# cadiz_mb_20140206_4.net
KiCad netlist of a schematic drawn in EAGLE
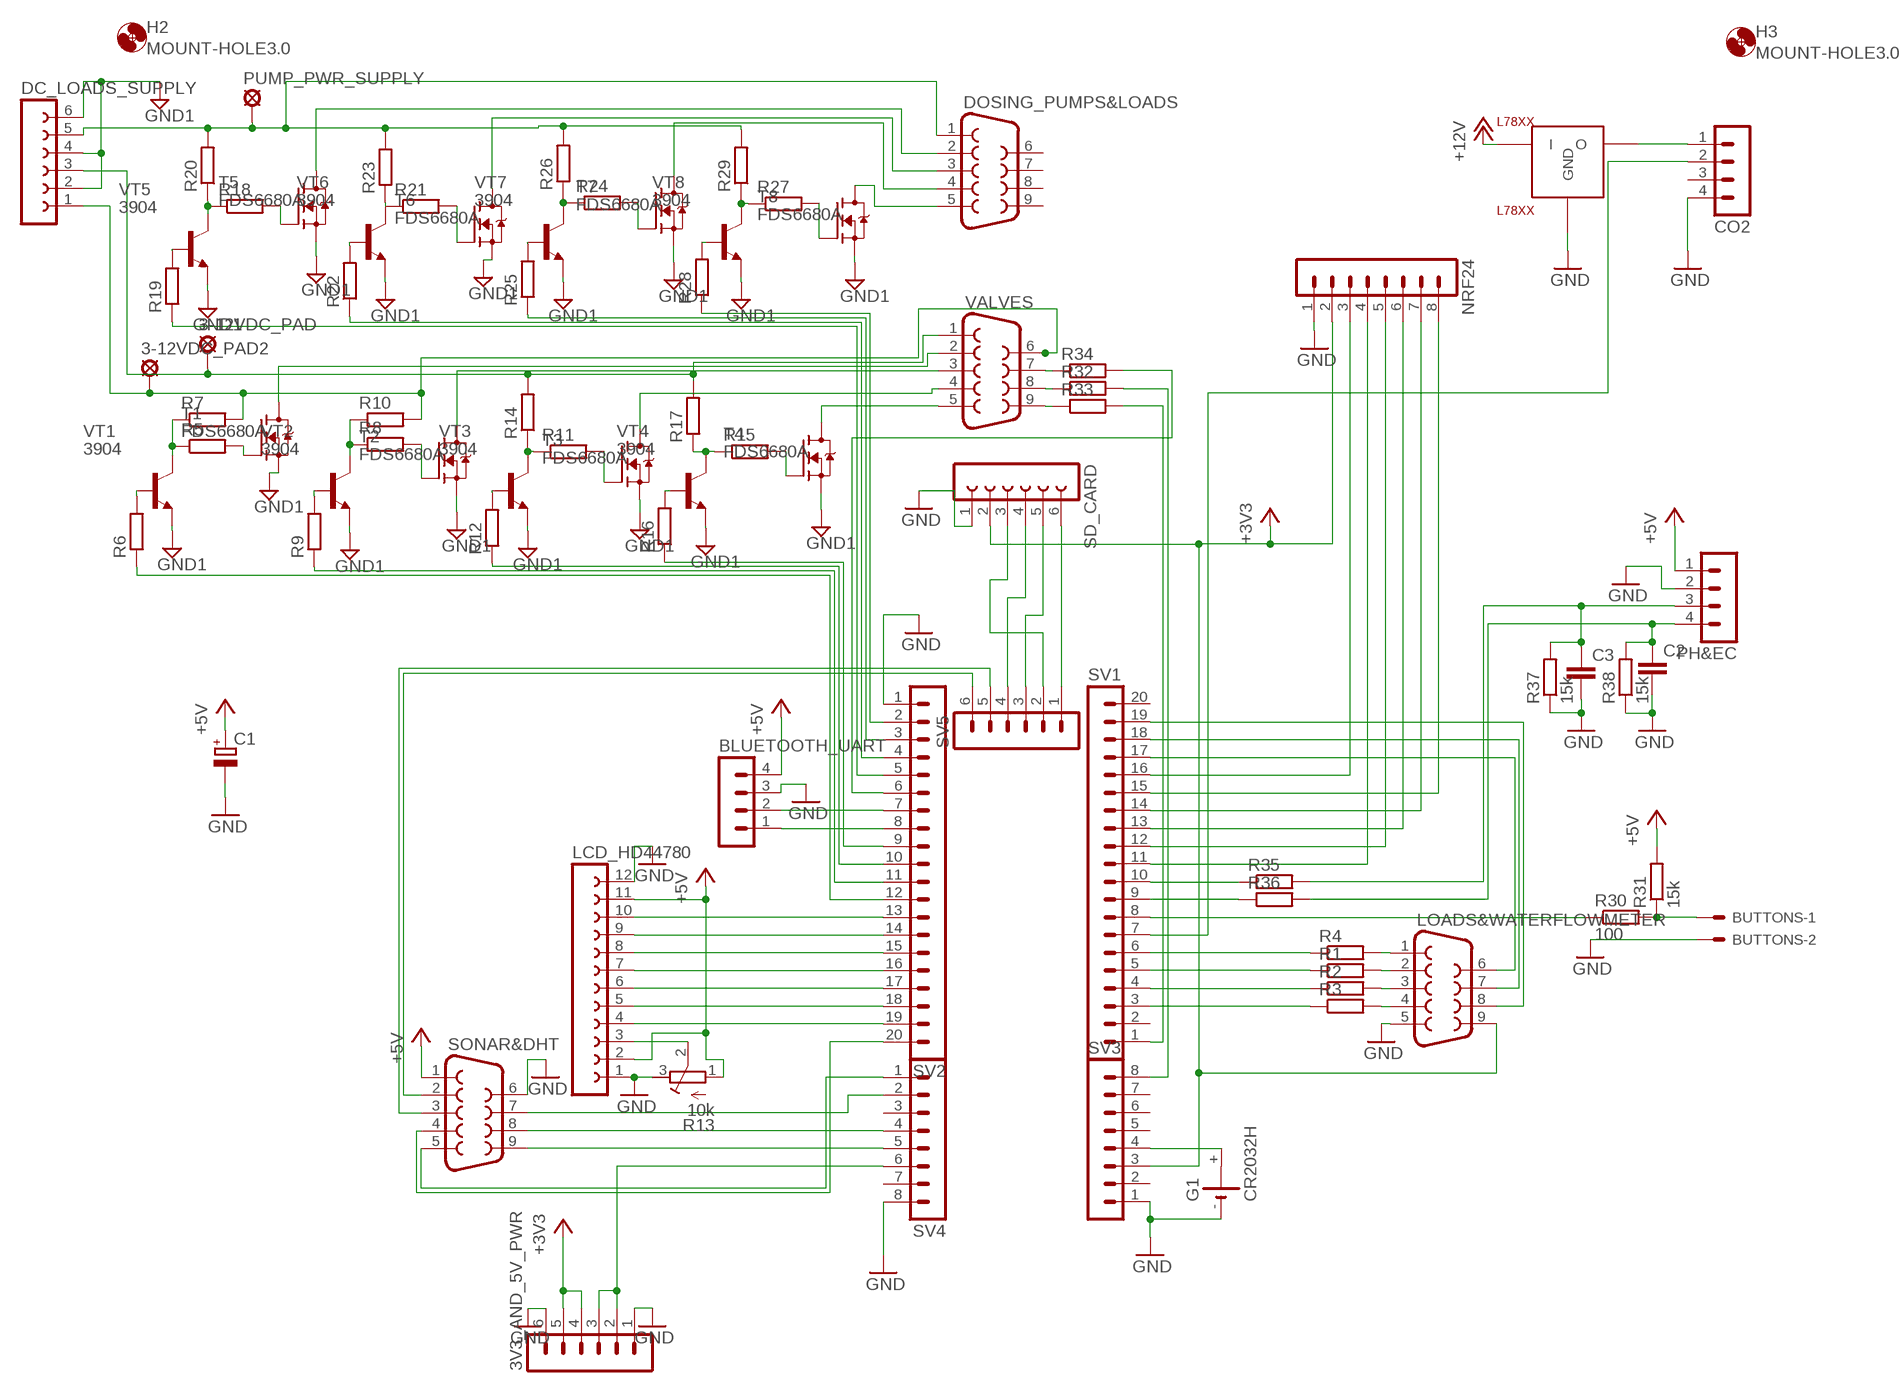
[diagram p0: schematic, sheet 1]

(export (version "E")
  (design (tool "Eeschema 10.0.6"))
  (components
    (comp (ref "3-12VDC_PAD")
      (value "LSP13")
      (footprint "eagle-import:LSP13")
      (libsource (lib "eagle-import") (part "LSP13"))
    )
    (comp (ref "3-12VDC_PAD2")
      (value "LSP13")
      (footprint "eagle-import:LSP13")
      (libsource (lib "eagle-import") (part "LSP13"))
    )
    (comp (ref "3V3_AND_5V_PWR")
      (value "MA06-1")
      (footprint "eagle-import:MA06-1")
      (libsource (lib "eagle-import") (part "MA06-1"))
    )
    (comp (ref "BLUETOOTH_UART")
      (value "MA04-1")
      (footprint "eagle-import:MA04-1")
      (libsource (lib "eagle-import") (part "MA04-1"))
    )
    (comp (ref "BUTTONS")
      (value "22-23-2021")
      (footprint "eagle-import:22-23-2021")
      (fields (field (name "MF") "MOLEX"))
      (libsource (lib "eagle-import") (part "22-23-2021"))
    )
    (comp (ref "C1")
      (value "CPOL-EUE5-13")
      (footprint "eagle-import:E5-13")
      (libsource (lib "eagle-import") (part "CPOL-EUE5-13"))
    )
    (comp (ref "C2")
      (value "C-EUC1206")
      (footprint "eagle-import:C1206")
      (libsource (lib "eagle-import") (part "C-EUC1206"))
    )
    (comp (ref "C3")
      (value "C-EUC1206")
      (footprint "eagle-import:C1206")
      (libsource (lib "eagle-import") (part "C-EUC1206"))
    )
    (comp (ref "CO2")
      (value "MA04-1")
      (footprint "eagle-import:MA04-1")
      (fields (field (name "OC_FARNELL") "unknown") (field (name "OC_NEWARK") "unknown"))
      (libsource (lib "eagle-import") (part "MA04-1"))
    )
    (comp (ref "DC_LOADS_SUPPLY")
      (value "FE06-1")
      (footprint "eagle-import:FE06")
      (libsource (lib "eagle-import") (part "FE06-1"))
    )
    (comp (ref "DOSING_PUMPS&LOADS")
      (value "F09HP")
      (footprint "eagle-import:F09HP")
      (libsource (lib "eagle-import") (part "F09HP"))
    )
    (comp (ref "G1")
      (value "CR2032H")
      (footprint "eagle-import:CR2032H")
      (libsource (lib "eagle-import") (part "CR2032H"))
    )
    (comp (ref "H2")
      (value "MOUNT-HOLE3.0")
      (footprint "eagle-import:3,0")
      (libsource (lib "eagle-import") (part "MOUNT-HOLE3.0"))
    )
    (comp (ref "H3")
      (value "MOUNT-HOLE3.0")
      (footprint "eagle-import:3,0")
      (libsource (lib "eagle-import") (part "MOUNT-HOLE3.0"))
    )
    (comp (ref "L7806")
      (value "L78XX")
      (footprint "eagle-import:TO220")
      (libsource (lib "eagle-import") (part "L78XX"))
    )
    (comp (ref "LCD_HD44780")
      (value "FE12-1")
      (footprint "eagle-import:FE12")
      (libsource (lib "eagle-import") (part "FE12-1"))
    )
    (comp (ref "LOADS&WATERFLOWMETER")
      (value "F09HP")
      (footprint "eagle-import:F09HP")
      (libsource (lib "eagle-import") (part "F09HP"))
    )
    (comp (ref "NRF24")
      (value "MA08-1")
      (footprint "eagle-import:MA08-1")
      (libsource (lib "eagle-import") (part "MA08-1"))
    )
    (comp (ref "PH&EC")
      (value "MA04-1")
      (footprint "eagle-import:MA04-1")
      (fields (field (name "OC_FARNELL") "unknown") (field (name "OC_NEWARK") "unknown"))
      (libsource (lib "eagle-import") (part "MA04-1"))
    )
    (comp (ref "PUMP_PWR_SUPPLY")
      (value "LSP13")
      (footprint "eagle-import:LSP13")
      (libsource (lib "eagle-import") (part "LSP13"))
    )
    (comp (ref "R1")
      (value "R-EU_M1206")
      (footprint "eagle-import:M1206")
      (libsource (lib "eagle-import") (part "R-EU_M1206"))
    )
    (comp (ref "R2")
      (value "R-EU_M1206")
      (footprint "eagle-import:M1206")
      (libsource (lib "eagle-import") (part "R-EU_M1206"))
    )
    (comp (ref "R3")
      (value "R-EU_M1206")
      (footprint "eagle-import:M1206")
      (libsource (lib "eagle-import") (part "R-EU_M1206"))
    )
    (comp (ref "R4")
      (value "R-EU_M1206")
      (footprint "eagle-import:M1206")
      (libsource (lib "eagle-import") (part "R-EU_M1206"))
    )
    (comp (ref "R5")
      (value "R-EU_M1206")
      (footprint "eagle-import:M1206")
      (libsource (lib "eagle-import") (part "R-EU_M1206"))
    )
    (comp (ref "R6")
      (value "R-EU_M1206")
      (footprint "eagle-import:M1206")
      (libsource (lib "eagle-import") (part "R-EU_M1206"))
    )
    (comp (ref "R7")
      (value "R-EU_M1206")
      (footprint "eagle-import:M1206")
      (libsource (lib "eagle-import") (part "R-EU_M1206"))
    )
    (comp (ref "R8")
      (value "R-EU_M1206")
      (footprint "eagle-import:M1206")
      (libsource (lib "eagle-import") (part "R-EU_M1206"))
    )
    (comp (ref "R9")
      (value "R-EU_M1206")
      (footprint "eagle-import:M1206")
      (libsource (lib "eagle-import") (part "R-EU_M1206"))
    )
    (comp (ref "R10")
      (value "R-EU_M1206")
      (footprint "eagle-import:M1206")
      (libsource (lib "eagle-import") (part "R-EU_M1206"))
    )
    (comp (ref "R11")
      (value "R-EU_M1206")
      (footprint "eagle-import:M1206")
      (libsource (lib "eagle-import") (part "R-EU_M1206"))
    )
    (comp (ref "R12")
      (value "R-EU_M1206")
      (footprint "eagle-import:M1206")
      (libsource (lib "eagle-import") (part "R-EU_M1206"))
    )
    (comp (ref "R13")
      (value "10k")
      (footprint "eagle-import:RTRIM3374")
      (libsource (lib "eagle-import") (part "R-TRIMM3374"))
    )
    (comp (ref "R14")
      (value "R-EU_M1206")
      (footprint "eagle-import:M1206")
      (libsource (lib "eagle-import") (part "R-EU_M1206"))
    )
    (comp (ref "R15")
      (value "R-EU_M1206")
      (footprint "eagle-import:M1206")
      (libsource (lib "eagle-import") (part "R-EU_M1206"))
    )
    (comp (ref "R16")
      (value "R-EU_M1206")
      (footprint "eagle-import:M1206")
      (libsource (lib "eagle-import") (part "R-EU_M1206"))
    )
    (comp (ref "R17")
      (value "R-EU_M1206")
      (footprint "eagle-import:M1206")
      (libsource (lib "eagle-import") (part "R-EU_M1206"))
    )
    (comp (ref "R18")
      (value "R-EU_M1206")
      (footprint "eagle-import:M1206")
      (libsource (lib "eagle-import") (part "R-EU_M1206"))
    )
    (comp (ref "R19")
      (value "R-EU_M1206")
      (footprint "eagle-import:M1206")
      (libsource (lib "eagle-import") (part "R-EU_M1206"))
    )
    (comp (ref "R20")
      (value "R-EU_M1206")
      (footprint "eagle-import:M1206")
      (libsource (lib "eagle-import") (part "R-EU_M1206"))
    )
    (comp (ref "R21")
      (value "R-EU_M1206")
      (footprint "eagle-import:M1206")
      (libsource (lib "eagle-import") (part "R-EU_M1206"))
    )
    (comp (ref "R22")
      (value "R-EU_M1206")
      (footprint "eagle-import:M1206")
      (libsource (lib "eagle-import") (part "R-EU_M1206"))
    )
    (comp (ref "R23")
      (value "R-EU_M1206")
      (footprint "eagle-import:M1206")
      (libsource (lib "eagle-import") (part "R-EU_M1206"))
    )
    (comp (ref "R24")
      (value "R-EU_M1206")
      (footprint "eagle-import:M1206")
      (libsource (lib "eagle-import") (part "R-EU_M1206"))
    )
    (comp (ref "R25")
      (value "R-EU_M1206")
      (footprint "eagle-import:M1206")
      (libsource (lib "eagle-import") (part "R-EU_M1206"))
    )
    (comp (ref "R26")
      (value "R-EU_M1206")
      (footprint "eagle-import:M1206")
      (libsource (lib "eagle-import") (part "R-EU_M1206"))
    )
    (comp (ref "R27")
      (value "R-EU_M1206")
      (footprint "eagle-import:M1206")
      (libsource (lib "eagle-import") (part "R-EU_M1206"))
    )
    (comp (ref "R28")
      (value "R-EU_M1206")
      (footprint "eagle-import:M1206")
      (libsource (lib "eagle-import") (part "R-EU_M1206"))
    )
    (comp (ref "R29")
      (value "R-EU_M1206")
      (footprint "eagle-import:M1206")
      (libsource (lib "eagle-import") (part "R-EU_M1206"))
    )
    (comp (ref "R30")
      (value "100")
      (footprint "eagle-import:M1206")
      (libsource (lib "eagle-import") (part "R-EU_M1206"))
    )
    (comp (ref "R31")
      (value "15k")
      (footprint "eagle-import:M1206")
      (libsource (lib "eagle-import") (part "R-EU_M1206"))
    )
    (comp (ref "R32")
      (value "R-EU_M1206")
      (footprint "eagle-import:M1206")
      (libsource (lib "eagle-import") (part "R-EU_M1206"))
    )
    (comp (ref "R33")
      (value "R-EU_M1206")
      (footprint "eagle-import:M1206")
      (libsource (lib "eagle-import") (part "R-EU_M1206"))
    )
    (comp (ref "R34")
      (value "R-EU_M1206")
      (footprint "eagle-import:M1206")
      (libsource (lib "eagle-import") (part "R-EU_M1206"))
    )
    (comp (ref "R35")
      (value "R-EU_M1206")
      (footprint "eagle-import:M1206")
      (libsource (lib "eagle-import") (part "R-EU_M1206"))
    )
    (comp (ref "R36")
      (value "R-EU_M1206")
      (footprint "eagle-import:M1206")
      (libsource (lib "eagle-import") (part "R-EU_M1206"))
    )
    (comp (ref "R37")
      (value "15k")
      (footprint "eagle-import:M1206")
      (libsource (lib "eagle-import") (part "R-EU_M1206"))
    )
    (comp (ref "R38")
      (value "15k")
      (footprint "eagle-import:M1206")
      (libsource (lib "eagle-import") (part "R-EU_M1206"))
    )
    (comp (ref "SD_CARD")
      (value "FE06-1")
      (footprint "eagle-import:FE06")
      (libsource (lib "eagle-import") (part "FE06-1"))
    )
    (comp (ref "SONAR&DHT")
      (value "F09HP")
      (footprint "eagle-import:F09HP")
      (libsource (lib "eagle-import") (part "F09HP"))
    )
    (comp (ref "SV1")
      (value "MA20-1")
      (footprint "eagle-import:MA20-1")
      (libsource (lib "eagle-import") (part "MA20-1"))
    )
    (comp (ref "SV2")
      (value "MA20-1")
      (footprint "eagle-import:MA20-1")
      (libsource (lib "eagle-import") (part "MA20-1"))
    )
    (comp (ref "SV3")
      (value "MA08-1")
      (footprint "eagle-import:MA08-1")
      (libsource (lib "eagle-import") (part "MA08-1"))
    )
    (comp (ref "SV4")
      (value "MA08-1")
      (footprint "eagle-import:MA08-1")
      (libsource (lib "eagle-import") (part "MA08-1"))
    )
    (comp (ref "SV5")
      (value "MA06-1")
      (footprint "eagle-import:MA06-1")
      (libsource (lib "eagle-import") (part "MA06-1"))
    )
    (comp (ref "T1")
      (value "FDS6680A")
      (footprint "eagle-import:SO8")
      (libsource (lib "eagle-import") (part "FDS6680A_SOP8"))
    )
    (comp (ref "T2")
      (value "FDS6680A")
      (footprint "eagle-import:SO8")
      (libsource (lib "eagle-import") (part "FDS6680A_SOP8"))
    )
    (comp (ref "T3")
      (value "FDS6680A")
      (footprint "eagle-import:SO8")
      (libsource (lib "eagle-import") (part "FDS6680A_SOP8"))
    )
    (comp (ref "T4")
      (value "FDS6680A")
      (footprint "eagle-import:SO8")
      (libsource (lib "eagle-import") (part "FDS6680A_SOP8"))
    )
    (comp (ref "T5")
      (value "FDS6680A")
      (footprint "eagle-import:SO8")
      (libsource (lib "eagle-import") (part "FDS6680A_SOP8"))
    )
    (comp (ref "T6")
      (value "FDS6680A")
      (footprint "eagle-import:SO8")
      (libsource (lib "eagle-import") (part "FDS6680A_SOP8"))
    )
    (comp (ref "T7")
      (value "FDS6680A")
      (footprint "eagle-import:SO8")
      (libsource (lib "eagle-import") (part "FDS6680A_SOP8"))
    )
    (comp (ref "T8")
      (value "FDS6680A")
      (footprint "eagle-import:SO8")
      (libsource (lib "eagle-import") (part "FDS6680A_SOP8"))
    )
    (comp (ref "VALVES")
      (value "F09HP")
      (footprint "eagle-import:F09HP")
      (libsource (lib "eagle-import") (part "F09HP"))
    )
    (comp (ref "VT1")
      (value "3904")
      (footprint "eagle-import:SOT23")
      (libsource (lib "eagle-import") (part "BC847"))
    )
    (comp (ref "VT2")
      (value "3904")
      (footprint "eagle-import:SOT23")
      (libsource (lib "eagle-import") (part "BC847"))
    )
    (comp (ref "VT3")
      (value "3904")
      (footprint "eagle-import:SOT23")
      (libsource (lib "eagle-import") (part "BC847"))
    )
    (comp (ref "VT4")
      (value "3904")
      (footprint "eagle-import:SOT23")
      (libsource (lib "eagle-import") (part "BC847"))
    )
    (comp (ref "VT5")
      (value "3904")
      (footprint "eagle-import:SOT23")
      (libsource (lib "eagle-import") (part "BC847"))
    )
    (comp (ref "VT6")
      (value "3904")
      (footprint "eagle-import:SOT23")
      (libsource (lib "eagle-import") (part "BC847"))
    )
    (comp (ref "VT7")
      (value "3904")
      (footprint "eagle-import:SOT23")
      (libsource (lib "eagle-import") (part "BC847"))
    )
    (comp (ref "VT8")
      (value "3904")
      (footprint "eagle-import:SOT23")
      (libsource (lib "eagle-import") (part "BC847"))
    )
  )
  (nets
    (net (code "1") (name "+3V3") (class "Default")
      (node (ref "3V3_AND_5V_PWR") (pin "4") (pinfunction "4_4") (pintype "passive"))
      (node (ref "3V3_AND_5V_PWR") (pin "5") (pinfunction "5_5") (pintype "passive"))
      (node (ref "LOADS&WATERFLOWMETER") (pin "9") (pinfunction "9_9") (pintype "passive"))
      (node (ref "NRF24") (pin "2") (pinfunction "2_2") (pintype "passive"))
      (node (ref "SD_CARD") (pin "2") (pinfunction "2_2") (pintype "passive"))
      (node (ref "SV3") (pin "3") (pinfunction "3_3") (pintype "passive"))
    )
    (net (code "2") (name "+5V") (class "Default")
      (node (ref "BLUETOOTH_UART") (pin "4") (pinfunction "4_4") (pintype "passive"))
      (node (ref "C1") (pin "+") (pinfunction "+_+") (pintype "passive"))
      (node (ref "LCD_HD44780") (pin "11") (pinfunction "11_11") (pintype "passive"))
      (node (ref "LCD_HD44780") (pin "2") (pinfunction "2_2") (pintype "passive"))
      (node (ref "PH&EC") (pin "1") (pinfunction "1_1") (pintype "passive"))
      (node (ref "R13") (pin "1") (pinfunction "E_1") (pintype "passive"))
      (node (ref "R31") (pin "2") (pinfunction "2_2") (pintype "passive"))
      (node (ref "SONAR&DHT") (pin "1") (pinfunction "1_1") (pintype "passive"))
    )
    (net (code "3") (name "+12V") (class "Default")
      (node (ref "L7806") (pin "IN") (pinfunction "I_IN") (pintype "power_in"))
    )
    (net (code "4") (name "GND") (class "Default")
      (node (ref "3V3_AND_5V_PWR") (pin "1") (pinfunction "1_1") (pintype "passive"))
      (node (ref "3V3_AND_5V_PWR") (pin "6") (pinfunction "6_6") (pintype "passive"))
      (node (ref "BLUETOOTH_UART") (pin "3") (pinfunction "3_3") (pintype "passive"))
      (node (ref "BUTTONS") (pin "2") (pinfunction "S_2") (pintype "passive"))
      (node (ref "C1") (pin "-") (pinfunction "-_-") (pintype "passive"))
      (node (ref "C2") (pin "2") (pinfunction "2_2") (pintype "passive"))
      (node (ref "C3") (pin "2") (pinfunction "2_2") (pintype "passive"))
      (node (ref "CO2") (pin "4") (pinfunction "4_4") (pintype "passive"))
      (node (ref "G1") (pin "-") (pinfunction "-_-") (pintype "passive"))
      (node (ref "L7806") (pin "GND") (pinfunction "GND_GND") (pintype "power_in"))
      (node (ref "LCD_HD44780") (pin "1") (pinfunction "1_1") (pintype "passive"))
      (node (ref "LCD_HD44780") (pin "12") (pinfunction "12_12") (pintype "passive"))
      (node (ref "LOADS&WATERFLOWMETER") (pin "5") (pinfunction "5_5") (pintype "passive"))
      (node (ref "NRF24") (pin "1") (pinfunction "1_1") (pintype "passive"))
      (node (ref "PH&EC") (pin "2") (pinfunction "2_2") (pintype "passive"))
      (node (ref "R13") (pin "3") (pinfunction "A_3") (pintype "passive"))
      (node (ref "R37") (pin "1") (pinfunction "1_1") (pintype "passive"))
      (node (ref "R38") (pin "1") (pinfunction "1_1") (pintype "passive"))
      (node (ref "SD_CARD") (pin "1") (pinfunction "1_1") (pintype "passive"))
      (node (ref "SONAR&DHT") (pin "6") (pinfunction "6_6") (pintype "passive"))
      (node (ref "SV2") (pin "1") (pinfunction "1_1") (pintype "passive"))
      (node (ref "SV3") (pin "1") (pinfunction "1_1") (pintype "passive"))
      (node (ref "SV4") (pin "8") (pinfunction "8_8") (pintype "passive"))
    )
    (net (code "5") (name "GND1") (class "Default")
      (node (ref "DC_LOADS_SUPPLY") (pin "2") (pinfunction "2_2") (pintype "passive"))
      (node (ref "DC_LOADS_SUPPLY") (pin "4") (pinfunction "4_4") (pintype "passive"))
      (node (ref "DC_LOADS_SUPPLY") (pin "6") (pinfunction "6_6") (pintype "passive"))
      (node (ref "T1") (pin "SOURCE") (pinfunction "S_SOURCE") (pintype "passive"))
      (node (ref "T2") (pin "SOURCE") (pinfunction "S_SOURCE") (pintype "passive"))
      (node (ref "T3") (pin "SOURCE") (pinfunction "S_SOURCE") (pintype "passive"))
      (node (ref "T4") (pin "SOURCE") (pinfunction "S_SOURCE") (pintype "passive"))
      (node (ref "T5") (pin "SOURCE") (pinfunction "S_SOURCE") (pintype "passive"))
      (node (ref "T6") (pin "SOURCE") (pinfunction "S_SOURCE") (pintype "passive"))
      (node (ref "T7") (pin "SOURCE") (pinfunction "S_SOURCE") (pintype "passive"))
      (node (ref "T8") (pin "SOURCE") (pinfunction "S_SOURCE") (pintype "passive"))
      (node (ref "VT1") (pin "2") (pinfunction "E_2") (pintype "passive"))
      (node (ref "VT2") (pin "2") (pinfunction "E_2") (pintype "passive"))
      (node (ref "VT3") (pin "2") (pinfunction "E_2") (pintype "passive"))
      (node (ref "VT4") (pin "2") (pinfunction "E_2") (pintype "passive"))
      (node (ref "VT5") (pin "2") (pinfunction "E_2") (pintype "passive"))
      (node (ref "VT6") (pin "2") (pinfunction "E_2") (pintype "passive"))
      (node (ref "VT7") (pin "2") (pinfunction "E_2") (pintype "passive"))
      (node (ref "VT8") (pin "2") (pinfunction "E_2") (pintype "passive"))
    )
    (net (code "6") (name "Net-(3-12VDC_PAD-PadMP)") (class "Default")
      (node (ref "3-12VDC_PAD") (pin "MP") (pinfunction "MP_MP") (pintype "passive"))
      (node (ref "DC_LOADS_SUPPLY") (pin "3") (pinfunction "3_3") (pintype "passive"))
      (node (ref "R14") (pin "2") (pinfunction "2_2") (pintype "passive"))
      (node (ref "R17") (pin "2") (pinfunction "2_2") (pintype "passive"))
      (node (ref "VALVES") (pin "1") (pinfunction "1_1") (pintype "passive"))
    )
    (net (code "7") (name "Net-(3-12VDC_PAD2-PadMP)") (class "Default")
      (node (ref "3-12VDC_PAD2") (pin "MP") (pinfunction "MP_MP") (pintype "passive"))
      (node (ref "DC_LOADS_SUPPLY") (pin "1") (pinfunction "1_1") (pintype "passive"))
      (node (ref "R10") (pin "2") (pinfunction "2_2") (pintype "passive"))
      (node (ref "R7") (pin "2") (pinfunction "2_2") (pintype "passive"))
      (node (ref "VALVES") (pin "6") (pinfunction "6_6") (pintype "passive"))
    )
    (net (code "8") (name "Net-(3V3_AND_5V_PWR-Pad2)") (class "Default")
      (node (ref "3V3_AND_5V_PWR") (pin "2") (pinfunction "2_2") (pintype "passive"))
      (node (ref "3V3_AND_5V_PWR") (pin "3") (pinfunction "3_3") (pintype "passive"))
      (node (ref "SV4") (pin "6") (pinfunction "6_6") (pintype "passive"))
    )
    (net (code "9") (name "Net-(BLUETOOTH_UART-Pad1)") (class "Default")
      (node (ref "BLUETOOTH_UART") (pin "1") (pinfunction "1_1") (pintype "passive"))
      (node (ref "SV2") (pin "8") (pinfunction "8_8") (pintype "passive"))
    )
    (net (code "10") (name "Net-(BLUETOOTH_UART-Pad2)") (class "Default")
      (node (ref "BLUETOOTH_UART") (pin "2") (pinfunction "2_2") (pintype "passive"))
      (node (ref "SV2") (pin "7") (pinfunction "7_7") (pintype "passive"))
    )
    (net (code "11") (name "Net-(BUTTONSA-S)") (class "Default")
      (node (ref "BUTTONS") (pin "1") (pinfunction "S_1") (pintype "passive"))
      (node (ref "R30") (pin "2") (pinfunction "2_2") (pintype "passive"))
      (node (ref "R31") (pin "1") (pinfunction "1_1") (pintype "passive"))
    )
    (net (code "12") (name "Net-(C2-Pad1)") (class "Default")
      (node (ref "C2") (pin "1") (pinfunction "1_1") (pintype "passive"))
      (node (ref "PH&EC") (pin "4") (pinfunction "4_4") (pintype "passive"))
      (node (ref "R36") (pin "2") (pinfunction "2_2") (pintype "passive"))
      (node (ref "R38") (pin "2") (pinfunction "2_2") (pintype "passive"))
    )
    (net (code "13") (name "Net-(C3-Pad1)") (class "Default")
      (node (ref "C3") (pin "1") (pinfunction "1_1") (pintype "passive"))
      (node (ref "PH&EC") (pin "3") (pinfunction "3_3") (pintype "passive"))
      (node (ref "R35") (pin "2") (pinfunction "2_2") (pintype "passive"))
      (node (ref "R37") (pin "2") (pinfunction "2_2") (pintype "passive"))
    )
    (net (code "14") (name "Net-(CO2-Pad2)") (class "Default")
      (node (ref "CO2") (pin "2") (pinfunction "2_2") (pintype "passive"))
      (node (ref "SV1") (pin "7") (pinfunction "7_7") (pintype "passive"))
    )
    (net (code "15") (name "Net-(DC_LOADS_SUPPLY-Pad5)") (class "Default")
      (node (ref "DC_LOADS_SUPPLY") (pin "5") (pinfunction "5_5") (pintype "passive"))
      (node (ref "DOSING_PUMPS&LOADS") (pin "1") (pinfunction "1_1") (pintype "passive"))
      (node (ref "PUMP_PWR_SUPPLY") (pin "MP") (pinfunction "MP_MP") (pintype "passive"))
      (node (ref "R20") (pin "2") (pinfunction "2_2") (pintype "passive"))
      (node (ref "R23") (pin "2") (pinfunction "2_2") (pintype "passive"))
      (node (ref "R26") (pin "2") (pinfunction "2_2") (pintype "passive"))
      (node (ref "R29") (pin "2") (pinfunction "2_2") (pintype "passive"))
    )
    (net (code "16") (name "Net-(G1-Pad+)") (class "Default")
      (node (ref "G1") (pin "+") (pinfunction "+_+") (pintype "passive"))
      (node (ref "SV3") (pin "4") (pinfunction "4_4") (pintype "passive"))
    )
    (net (code "17") (name "Net-(L7806-O)") (class "Default")
      (node (ref "CO2") (pin "1") (pinfunction "1_1") (pintype "passive"))
      (node (ref "L7806") (pin "OUT") (pinfunction "O_OUT") (pintype "power_in"))
    )
    (net (code "18") (name "Net-(LCD_HD44780-Pad4)") (class "Default")
      (node (ref "LCD_HD44780") (pin "4") (pinfunction "4_4") (pintype "passive"))
      (node (ref "SV2") (pin "19") (pinfunction "19_19") (pintype "passive"))
    )
    (net (code "19") (name "Net-(LCD_HD44780-Pad5)") (class "Default")
      (node (ref "LCD_HD44780") (pin "5") (pinfunction "5_5") (pintype "passive"))
      (node (ref "SV2") (pin "18") (pinfunction "18_18") (pintype "passive"))
    )
    (net (code "20") (name "Net-(LCD_HD44780-Pad6)") (class "Default")
      (node (ref "LCD_HD44780") (pin "6") (pinfunction "6_6") (pintype "passive"))
      (node (ref "SV2") (pin "17") (pinfunction "17_17") (pintype "passive"))
    )
    (net (code "21") (name "Net-(LCD_HD44780-Pad7)") (class "Default")
      (node (ref "LCD_HD44780") (pin "7") (pinfunction "7_7") (pintype "passive"))
      (node (ref "SV2") (pin "16") (pinfunction "16_16") (pintype "passive"))
    )
    (net (code "22") (name "Net-(LCD_HD44780-Pad8)") (class "Default")
      (node (ref "LCD_HD44780") (pin "8") (pinfunction "8_8") (pintype "passive"))
      (node (ref "SV2") (pin "15") (pinfunction "15_15") (pintype "passive"))
    )
    (net (code "23") (name "Net-(LCD_HD44780-Pad9)") (class "Default")
      (node (ref "LCD_HD44780") (pin "9") (pinfunction "9_9") (pintype "passive"))
      (node (ref "SV2") (pin "14") (pinfunction "14_14") (pintype "passive"))
    )
    (net (code "24") (name "Net-(LCD_HD44780-Pad10)") (class "Default")
      (node (ref "LCD_HD44780") (pin "10") (pinfunction "10_10") (pintype "passive"))
      (node (ref "SV2") (pin "13") (pinfunction "13_13") (pintype "passive"))
    )
    (net (code "25") (name "Net-(LOADS&WATERFLOWMETER-Pad1)") (class "Default")
      (node (ref "LOADS&WATERFLOWMETER") (pin "1") (pinfunction "1_1") (pintype "passive"))
      (node (ref "R4") (pin "2") (pinfunction "2_2") (pintype "passive"))
    )
    (net (code "26") (name "Net-(LOADS&WATERFLOWMETER-Pad2)") (class "Default")
      (node (ref "LOADS&WATERFLOWMETER") (pin "2") (pinfunction "2_2") (pintype "passive"))
      (node (ref "R1") (pin "2") (pinfunction "2_2") (pintype "passive"))
    )
    (net (code "27") (name "Net-(LOADS&WATERFLOWMETER-Pad3)") (class "Default")
      (node (ref "LOADS&WATERFLOWMETER") (pin "3") (pinfunction "3_3") (pintype "passive"))
      (node (ref "R2") (pin "2") (pinfunction "2_2") (pintype "passive"))
    )
    (net (code "28") (name "Net-(LOADS&WATERFLOWMETER-Pad4)") (class "Default")
      (node (ref "LOADS&WATERFLOWMETER") (pin "4") (pinfunction "4_4") (pintype "passive"))
      (node (ref "R3") (pin "2") (pinfunction "2_2") (pintype "passive"))
    )
    (net (code "29") (name "Net-(LOADS&WATERFLOWMETER-Pad6)") (class "Default")
      (node (ref "LOADS&WATERFLOWMETER") (pin "6") (pinfunction "6_6") (pintype "passive"))
      (node (ref "SV1") (pin "17") (pinfunction "17_17") (pintype "passive"))
    )
    (net (code "30") (name "Net-(LOADS&WATERFLOWMETER-Pad7)") (class "Default")
      (node (ref "LOADS&WATERFLOWMETER") (pin "7") (pinfunction "7_7") (pintype "passive"))
      (node (ref "SV1") (pin "18") (pinfunction "18_18") (pintype "passive"))
    )
    (net (code "31") (name "Net-(LOADS&WATERFLOWMETER-Pad8)") (class "Default")
      (node (ref "LOADS&WATERFLOWMETER") (pin "8") (pinfunction "8_8") (pintype "passive"))
      (node (ref "SV1") (pin "19") (pinfunction "19_19") (pintype "passive"))
    )
    (net (code "32") (name "Net-(NRF24-Pad3)") (class "Default")
      (node (ref "NRF24") (pin "3") (pinfunction "3_3") (pintype "passive"))
      (node (ref "SV1") (pin "16") (pinfunction "16_16") (pintype "passive"))
    )
    (net (code "33") (name "Net-(NRF24-Pad4)") (class "Default")
      (node (ref "NRF24") (pin "4") (pinfunction "4_4") (pintype "passive"))
      (node (ref "SV1") (pin "11") (pinfunction "11_11") (pintype "passive"))
    )
    (net (code "34") (name "Net-(NRF24-Pad5)") (class "Default")
      (node (ref "NRF24") (pin "5") (pinfunction "5_5") (pintype "passive"))
      (node (ref "SV1") (pin "12") (pinfunction "12_12") (pintype "passive"))
    )
    (net (code "35") (name "Net-(NRF24-Pad6)") (class "Default")
      (node (ref "NRF24") (pin "6") (pinfunction "6_6") (pintype "passive"))
      (node (ref "SV1") (pin "13") (pinfunction "13_13") (pintype "passive"))
    )
    (net (code "36") (name "Net-(NRF24-Pad7)") (class "Default")
      (node (ref "NRF24") (pin "7") (pinfunction "7_7") (pintype "passive"))
      (node (ref "SV1") (pin "14") (pinfunction "14_14") (pintype "passive"))
    )
    (net (code "37") (name "Net-(NRF24-Pad8)") (class "Default")
      (node (ref "NRF24") (pin "8") (pinfunction "8_8") (pintype "passive"))
      (node (ref "SV1") (pin "15") (pinfunction "15_15") (pintype "passive"))
    )
    (net (code "38") (name "Net-(R1-Pad1)") (class "Default")
      (node (ref "R1") (pin "1") (pinfunction "1_1") (pintype "passive"))
      (node (ref "SV1") (pin "5") (pinfunction "5_5") (pintype "passive"))
    )
    (net (code "39") (name "Net-(R2-Pad1)") (class "Default")
      (node (ref "R2") (pin "1") (pinfunction "1_1") (pintype "passive"))
      (node (ref "SV1") (pin "4") (pinfunction "4_4") (pintype "passive"))
    )
    (net (code "40") (name "Net-(R3-Pad1)") (class "Default")
      (node (ref "R3") (pin "1") (pinfunction "1_1") (pintype "passive"))
      (node (ref "SV1") (pin "3") (pinfunction "3_3") (pintype "passive"))
    )
    (net (code "41") (name "Net-(R4-Pad1)") (class "Default")
      (node (ref "R4") (pin "1") (pinfunction "1_1") (pintype "passive"))
      (node (ref "SV1") (pin "6") (pinfunction "6_6") (pintype "passive"))
    )
    (net (code "42") (name "Net-(R6-Pad1)") (class "Default")
      (node (ref "R6") (pin "1") (pinfunction "1_1") (pintype "passive"))
      (node (ref "SV2") (pin "12") (pinfunction "12_12") (pintype "passive"))
    )
    (net (code "43") (name "Net-(R9-Pad1)") (class "Default")
      (node (ref "R9") (pin "1") (pinfunction "1_1") (pintype "passive"))
      (node (ref "SV2") (pin "11") (pinfunction "11_11") (pintype "passive"))
    )
    (net (code "44") (name "Net-(R12-Pad1)") (class "Default")
      (node (ref "R12") (pin "1") (pinfunction "1_1") (pintype "passive"))
      (node (ref "SV2") (pin "10") (pinfunction "10_10") (pintype "passive"))
    )
    (net (code "45") (name "Net-(R13-S)") (class "Default")
      (node (ref "LCD_HD44780") (pin "3") (pinfunction "3_3") (pintype "passive"))
      (node (ref "R13") (pin "2") (pinfunction "S_2") (pintype "passive"))
    )
    (net (code "46") (name "Net-(R16-Pad1)") (class "Default")
      (node (ref "R16") (pin "1") (pinfunction "1_1") (pintype "passive"))
      (node (ref "SV2") (pin "9") (pinfunction "9_9") (pintype "passive"))
    )
    (net (code "47") (name "Net-(R19-Pad1)") (class "Default")
      (node (ref "R19") (pin "1") (pinfunction "1_1") (pintype "passive"))
      (node (ref "SV2") (pin "5") (pinfunction "5_5") (pintype "passive"))
    )
    (net (code "48") (name "Net-(R22-Pad1)") (class "Default")
      (node (ref "R22") (pin "1") (pinfunction "1_1") (pintype "passive"))
      (node (ref "SV2") (pin "4") (pinfunction "4_4") (pintype "passive"))
    )
    (net (code "49") (name "Net-(R25-Pad1)") (class "Default")
      (node (ref "R25") (pin "1") (pinfunction "1_1") (pintype "passive"))
      (node (ref "SV2") (pin "3") (pinfunction "3_3") (pintype "passive"))
    )
    (net (code "50") (name "Net-(R28-Pad1)") (class "Default")
      (node (ref "R28") (pin "1") (pinfunction "1_1") (pintype "passive"))
      (node (ref "SV2") (pin "2") (pinfunction "2_2") (pintype "passive"))
    )
    (net (code "51") (name "Net-(R30-Pad1)") (class "Default")
      (node (ref "R30") (pin "1") (pinfunction "1_1") (pintype "passive"))
      (node (ref "SV1") (pin "8") (pinfunction "8_8") (pintype "passive"))
    )
    (net (code "52") (name "Net-(R32-Pad1)") (class "Default")
      (node (ref "R32") (pin "1") (pinfunction "1_1") (pintype "passive"))
      (node (ref "VALVES") (pin "8") (pinfunction "8_8") (pintype "passive"))
    )
    (net (code "53") (name "Net-(R32-Pad2)") (class "Default")
      (node (ref "R32") (pin "2") (pinfunction "2_2") (pintype "passive"))
      (node (ref "SV3") (pin "8") (pinfunction "8_8") (pintype "passive"))
    )
    (net (code "54") (name "Net-(R33-Pad1)") (class "Default")
      (node (ref "R33") (pin "1") (pinfunction "1_1") (pintype "passive"))
      (node (ref "VALVES") (pin "9") (pinfunction "9_9") (pintype "passive"))
    )
    (net (code "55") (name "Net-(R33-Pad2)") (class "Default")
      (node (ref "R33") (pin "2") (pinfunction "2_2") (pintype "passive"))
      (node (ref "SV1") (pin "1") (pinfunction "1_1") (pintype "passive"))
    )
    (net (code "56") (name "Net-(R34-Pad1)") (class "Default")
      (node (ref "R34") (pin "1") (pinfunction "1_1") (pintype "passive"))
      (node (ref "VALVES") (pin "7") (pinfunction "7_7") (pintype "passive"))
    )
    (net (code "57") (name "Net-(R34-Pad2)") (class "Default")
      (node (ref "R34") (pin "2") (pinfunction "2_2") (pintype "passive"))
      (node (ref "SV2") (pin "6") (pinfunction "6_6") (pintype "passive"))
    )
    (net (code "58") (name "Net-(R35-Pad1)") (class "Default")
      (node (ref "R35") (pin "1") (pinfunction "1_1") (pintype "passive"))
      (node (ref "SV1") (pin "10") (pinfunction "10_10") (pintype "passive"))
    )
    (net (code "59") (name "Net-(R36-Pad1)") (class "Default")
      (node (ref "R36") (pin "1") (pinfunction "1_1") (pintype "passive"))
      (node (ref "SV1") (pin "9") (pinfunction "9_9") (pintype "passive"))
    )
    (net (code "60") (name "Net-(SD_CARD-Pad3)") (class "Default")
      (node (ref "SD_CARD") (pin "3") (pinfunction "3_3") (pintype "passive"))
      (node (ref "SV5") (pin "2") (pinfunction "2_2") (pintype "passive"))
    )
    (net (code "61") (name "Net-(SD_CARD-Pad4)") (class "Default")
      (node (ref "SD_CARD") (pin "4") (pinfunction "4_4") (pintype "passive"))
      (node (ref "SV5") (pin "4") (pinfunction "4_4") (pintype "passive"))
    )
    (net (code "62") (name "Net-(SD_CARD-Pad5)") (class "Default")
      (node (ref "SD_CARD") (pin "5") (pinfunction "5_5") (pintype "passive"))
      (node (ref "SV5") (pin "3") (pinfunction "3_3") (pintype "passive"))
    )
    (net (code "63") (name "Net-(SD_CARD-Pad6)") (class "Default")
      (node (ref "SD_CARD") (pin "6") (pinfunction "6_6") (pintype "passive"))
      (node (ref "SV5") (pin "1") (pinfunction "1_1") (pintype "passive"))
    )
    (net (code "64") (name "Net-(SONAR&DHT-Pad2)") (class "Default")
      (node (ref "SONAR&DHT") (pin "2") (pinfunction "2_2") (pintype "passive"))
      (node (ref "SV5") (pin "6") (pinfunction "6_6") (pintype "passive"))
    )
    (net (code "65") (name "Net-(SONAR&DHT-Pad3)") (class "Default")
      (node (ref "SONAR&DHT") (pin "3") (pinfunction "3_3") (pintype "passive"))
      (node (ref "SV5") (pin "5") (pinfunction "5_5") (pintype "passive"))
    )
    (net (code "66") (name "Net-(SONAR&DHT-Pad4)") (class "Default")
      (node (ref "SONAR&DHT") (pin "4") (pinfunction "4_4") (pintype "passive"))
      (node (ref "SV2") (pin "20") (pinfunction "20_20") (pintype "passive"))
    )
    (net (code "67") (name "Net-(SONAR&DHT-Pad5)") (class "Default")
      (node (ref "SONAR&DHT") (pin "5") (pinfunction "5_5") (pintype "passive"))
      (node (ref "SV4") (pin "1") (pinfunction "1_1") (pintype "passive"))
    )
    (net (code "68") (name "Net-(SONAR&DHT-Pad7)") (class "Default")
      (node (ref "SONAR&DHT") (pin "7") (pinfunction "7_7") (pintype "passive"))
      (node (ref "SV4") (pin "2") (pinfunction "2_2") (pintype "passive"))
    )
    (net (code "69") (name "Net-(SONAR&DHT-Pad8)") (class "Default")
      (node (ref "SONAR&DHT") (pin "8") (pinfunction "8_8") (pintype "passive"))
      (node (ref "SV4") (pin "4") (pinfunction "4_4") (pintype "passive"))
    )
    (net (code "70") (name "Net-(SONAR&DHT-Pad9)") (class "Default")
      (node (ref "SONAR&DHT") (pin "9") (pinfunction "9_9") (pintype "passive"))
      (node (ref "SV4") (pin "5") (pinfunction "5_5") (pintype "passive"))
    )
    (net (code "71") (name "Net-(T1-D)") (class "Default")
      (node (ref "T1") (pin "DRAIN") (pinfunction "D_DRAIN") (pintype "passive"))
      (node (ref "VALVES") (pin "2") (pinfunction "2_2") (pintype "passive"))
    )
    (net (code "72") (name "Net-(T1-G)") (class "Default")
      (node (ref "R5") (pin "2") (pinfunction "2_2") (pintype "passive"))
      (node (ref "T1") (pin "GATE") (pinfunction "G_GATE") (pintype "passive"))
    )
    (net (code "73") (name "Net-(T2-D)") (class "Default")
      (node (ref "T2") (pin "DRAIN") (pinfunction "D_DRAIN") (pintype "passive"))
      (node (ref "VALVES") (pin "3") (pinfunction "3_3") (pintype "passive"))
    )
    (net (code "74") (name "Net-(T2-G)") (class "Default")
      (node (ref "R8") (pin "2") (pinfunction "2_2") (pintype "passive"))
      (node (ref "T2") (pin "GATE") (pinfunction "G_GATE") (pintype "passive"))
    )
    (net (code "75") (name "Net-(T3-D)") (class "Default")
      (node (ref "T3") (pin "DRAIN") (pinfunction "D_DRAIN") (pintype "passive"))
      (node (ref "VALVES") (pin "4") (pinfunction "4_4") (pintype "passive"))
    )
    (net (code "76") (name "Net-(T3-G)") (class "Default")
      (node (ref "R11") (pin "2") (pinfunction "2_2") (pintype "passive"))
      (node (ref "T3") (pin "GATE") (pinfunction "G_GATE") (pintype "passive"))
    )
    (net (code "77") (name "Net-(T4-D)") (class "Default")
      (node (ref "T4") (pin "DRAIN") (pinfunction "D_DRAIN") (pintype "passive"))
      (node (ref "VALVES") (pin "5") (pinfunction "5_5") (pintype "passive"))
    )
    (net (code "78") (name "Net-(T4-G)") (class "Default")
      (node (ref "R15") (pin "2") (pinfunction "2_2") (pintype "passive"))
      (node (ref "T4") (pin "GATE") (pinfunction "G_GATE") (pintype "passive"))
    )
    (net (code "79") (name "Net-(T5-D)") (class "Default")
      (node (ref "DOSING_PUMPS&LOADS") (pin "2") (pinfunction "2_2") (pintype "passive"))
      (node (ref "T5") (pin "DRAIN") (pinfunction "D_DRAIN") (pintype "passive"))
    )
    (net (code "80") (name "Net-(T5-G)") (class "Default")
      (node (ref "R18") (pin "2") (pinfunction "2_2") (pintype "passive"))
      (node (ref "T5") (pin "GATE") (pinfunction "G_GATE") (pintype "passive"))
    )
    (net (code "81") (name "Net-(T6-D)") (class "Default")
      (node (ref "DOSING_PUMPS&LOADS") (pin "3") (pinfunction "3_3") (pintype "passive"))
      (node (ref "T6") (pin "DRAIN") (pinfunction "D_DRAIN") (pintype "passive"))
    )
    (net (code "82") (name "Net-(T6-G)") (class "Default")
      (node (ref "R21") (pin "2") (pinfunction "2_2") (pintype "passive"))
      (node (ref "T6") (pin "GATE") (pinfunction "G_GATE") (pintype "passive"))
    )
    (net (code "83") (name "Net-(T7-D)") (class "Default")
      (node (ref "DOSING_PUMPS&LOADS") (pin "4") (pinfunction "4_4") (pintype "passive"))
      (node (ref "T7") (pin "DRAIN") (pinfunction "D_DRAIN") (pintype "passive"))
    )
    (net (code "84") (name "Net-(T7-G)") (class "Default")
      (node (ref "R24") (pin "2") (pinfunction "2_2") (pintype "passive"))
      (node (ref "T7") (pin "GATE") (pinfunction "G_GATE") (pintype "passive"))
    )
    (net (code "85") (name "Net-(T8-D)") (class "Default")
      (node (ref "DOSING_PUMPS&LOADS") (pin "5") (pinfunction "5_5") (pintype "passive"))
      (node (ref "T8") (pin "DRAIN") (pinfunction "D_DRAIN") (pintype "passive"))
    )
    (net (code "86") (name "Net-(T8-G)") (class "Default")
      (node (ref "R27") (pin "2") (pinfunction "2_2") (pintype "passive"))
      (node (ref "T8") (pin "GATE") (pinfunction "G_GATE") (pintype "passive"))
    )
    (net (code "87") (name "Net-(VT1-B)") (class "Default")
      (node (ref "R6") (pin "2") (pinfunction "2_2") (pintype "passive"))
      (node (ref "VT1") (pin "1") (pinfunction "B_1") (pintype "passive"))
    )
    (net (code "88") (name "Net-(VT1-C)") (class "Default")
      (node (ref "R5") (pin "1") (pinfunction "1_1") (pintype "passive"))
      (node (ref "R7") (pin "1") (pinfunction "1_1") (pintype "passive"))
      (node (ref "VT1") (pin "3") (pinfunction "C_3") (pintype "passive"))
    )
    (net (code "89") (name "Net-(VT2-B)") (class "Default")
      (node (ref "R9") (pin "2") (pinfunction "2_2") (pintype "passive"))
      (node (ref "VT2") (pin "1") (pinfunction "B_1") (pintype "passive"))
    )
    (net (code "90") (name "Net-(VT2-C)") (class "Default")
      (node (ref "R10") (pin "1") (pinfunction "1_1") (pintype "passive"))
      (node (ref "R8") (pin "1") (pinfunction "1_1") (pintype "passive"))
      (node (ref "VT2") (pin "3") (pinfunction "C_3") (pintype "passive"))
    )
    (net (code "91") (name "Net-(VT3-B)") (class "Default")
      (node (ref "R12") (pin "2") (pinfunction "2_2") (pintype "passive"))
      (node (ref "VT3") (pin "1") (pinfunction "B_1") (pintype "passive"))
    )
    (net (code "92") (name "Net-(VT3-C)") (class "Default")
      (node (ref "R11") (pin "1") (pinfunction "1_1") (pintype "passive"))
      (node (ref "R14") (pin "1") (pinfunction "1_1") (pintype "passive"))
      (node (ref "VT3") (pin "3") (pinfunction "C_3") (pintype "passive"))
    )
    (net (code "93") (name "Net-(VT4-B)") (class "Default")
      (node (ref "R16") (pin "2") (pinfunction "2_2") (pintype "passive"))
      (node (ref "VT4") (pin "1") (pinfunction "B_1") (pintype "passive"))
    )
    (net (code "94") (name "Net-(VT4-C)") (class "Default")
      (node (ref "R15") (pin "1") (pinfunction "1_1") (pintype "passive"))
      (node (ref "R17") (pin "1") (pinfunction "1_1") (pintype "passive"))
      (node (ref "VT4") (pin "3") (pinfunction "C_3") (pintype "passive"))
    )
    (net (code "95") (name "Net-(VT5-B)") (class "Default")
      (node (ref "R19") (pin "2") (pinfunction "2_2") (pintype "passive"))
      (node (ref "VT5") (pin "1") (pinfunction "B_1") (pintype "passive"))
    )
    (net (code "96") (name "Net-(VT5-C)") (class "Default")
      (node (ref "R18") (pin "1") (pinfunction "1_1") (pintype "passive"))
      (node (ref "R20") (pin "1") (pinfunction "1_1") (pintype "passive"))
      (node (ref "VT5") (pin "3") (pinfunction "C_3") (pintype "passive"))
    )
    (net (code "97") (name "Net-(VT6-B)") (class "Default")
      (node (ref "R22") (pin "2") (pinfunction "2_2") (pintype "passive"))
      (node (ref "VT6") (pin "1") (pinfunction "B_1") (pintype "passive"))
    )
    (net (code "98") (name "Net-(VT6-C)") (class "Default")
      (node (ref "R21") (pin "1") (pinfunction "1_1") (pintype "passive"))
      (node (ref "R23") (pin "1") (pinfunction "1_1") (pintype "passive"))
      (node (ref "VT6") (pin "3") (pinfunction "C_3") (pintype "passive"))
    )
    (net (code "99") (name "Net-(VT7-B)") (class "Default")
      (node (ref "R25") (pin "2") (pinfunction "2_2") (pintype "passive"))
      (node (ref "VT7") (pin "1") (pinfunction "B_1") (pintype "passive"))
    )
    (net (code "100") (name "Net-(VT7-C)") (class "Default")
      (node (ref "R24") (pin "1") (pinfunction "1_1") (pintype "passive"))
      (node (ref "R26") (pin "1") (pinfunction "1_1") (pintype "passive"))
      (node (ref "VT7") (pin "3") (pinfunction "C_3") (pintype "passive"))
    )
    (net (code "101") (name "Net-(VT8-B)") (class "Default")
      (node (ref "R28") (pin "2") (pinfunction "2_2") (pintype "passive"))
      (node (ref "VT8") (pin "1") (pinfunction "B_1") (pintype "passive"))
    )
    (net (code "102") (name "Net-(VT8-C)") (class "Default")
      (node (ref "R27") (pin "1") (pinfunction "1_1") (pintype "passive"))
      (node (ref "R29") (pin "1") (pinfunction "1_1") (pintype "passive"))
      (node (ref "VT8") (pin "3") (pinfunction "C_3") (pintype "passive"))
    )
    (net (code "103") (name "unconnected-(CO2-Pad3)") (class "Default")
      (node (ref "CO2") (pin "3") (pinfunction "3_3") (pintype "passive"))
    )
    (net (code "104") (name "unconnected-(DOSING_PUMPS&LOADS-Pad6)") (class "Default")
      (node (ref "DOSING_PUMPS&LOADS") (pin "6") (pinfunction "6_6") (pintype "passive"))
    )
    (net (code "105") (name "unconnected-(DOSING_PUMPS&LOADS-Pad7)") (class "Default")
      (node (ref "DOSING_PUMPS&LOADS") (pin "7") (pinfunction "7_7") (pintype "passive"))
    )
    (net (code "106") (name "unconnected-(DOSING_PUMPS&LOADS-Pad8)") (class "Default")
      (node (ref "DOSING_PUMPS&LOADS") (pin "8") (pinfunction "8_8") (pintype "passive"))
    )
    (net (code "107") (name "unconnected-(DOSING_PUMPS&LOADS-Pad9)") (class "Default")
      (node (ref "DOSING_PUMPS&LOADS") (pin "9") (pinfunction "9_9") (pintype "passive"))
    )
    (net (code "108") (name "unconnected-(G1-+-Pad+@1)") (class "Default")
      (node (ref "G1") (pin "+@1") (pinfunction "+_+@1") (pintype "passive"))
    )
    (net (code "109") (name "unconnected-(SV1-Pad2)") (class "Default")
      (node (ref "SV1") (pin "2") (pinfunction "2_2") (pintype "passive"))
    )
    (net (code "110") (name "unconnected-(SV1-Pad20)") (class "Default")
      (node (ref "SV1") (pin "20") (pinfunction "20_20") (pintype "passive"))
    )
    (net (code "111") (name "unconnected-(SV3-Pad2)") (class "Default")
      (node (ref "SV3") (pin "2") (pinfunction "2_2") (pintype "passive"))
    )
    (net (code "112") (name "unconnected-(SV3-Pad5)") (class "Default")
      (node (ref "SV3") (pin "5") (pinfunction "5_5") (pintype "passive"))
    )
    (net (code "113") (name "unconnected-(SV3-Pad6)") (class "Default")
      (node (ref "SV3") (pin "6") (pinfunction "6_6") (pintype "passive"))
    )
    (net (code "114") (name "unconnected-(SV3-Pad7)") (class "Default")
      (node (ref "SV3") (pin "7") (pinfunction "7_7") (pintype "passive"))
    )
    (net (code "115") (name "unconnected-(SV4-Pad3)") (class "Default")
      (node (ref "SV4") (pin "3") (pinfunction "3_3") (pintype "passive"))
    )
    (net (code "116") (name "unconnected-(SV4-Pad7)") (class "Default")
      (node (ref "SV4") (pin "7") (pinfunction "7_7") (pintype "passive"))
    )
  )
)
